# turbo.net
KiCad netlist of a schematic drawn in EAGLE
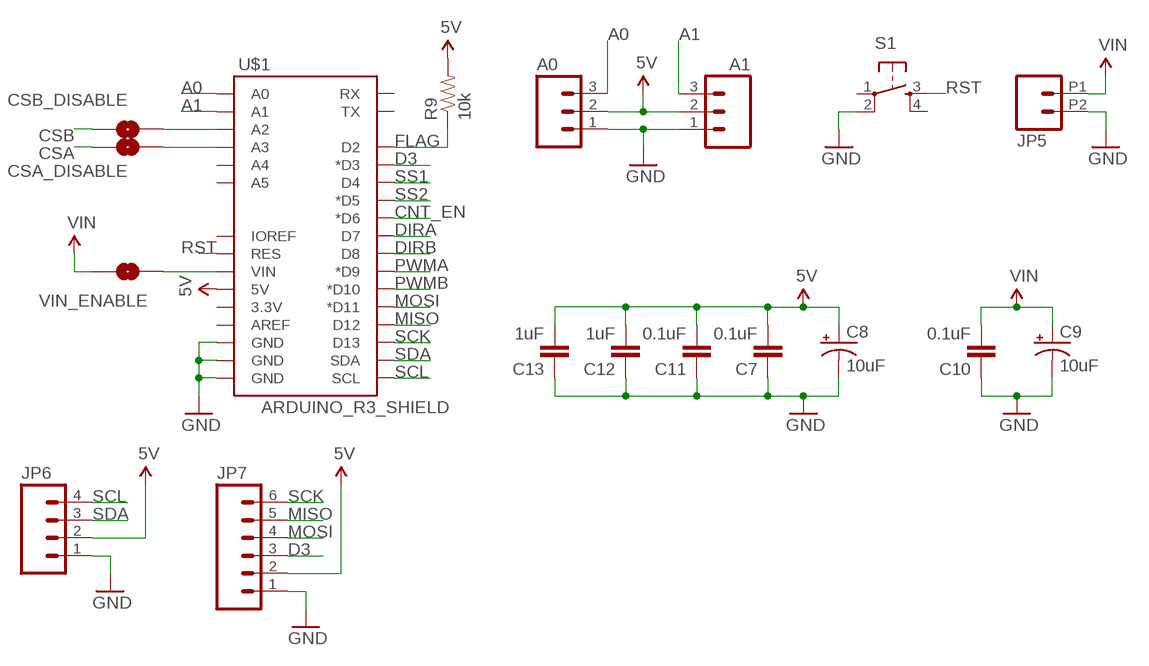
[diagram p0: schematic, sheet 1]
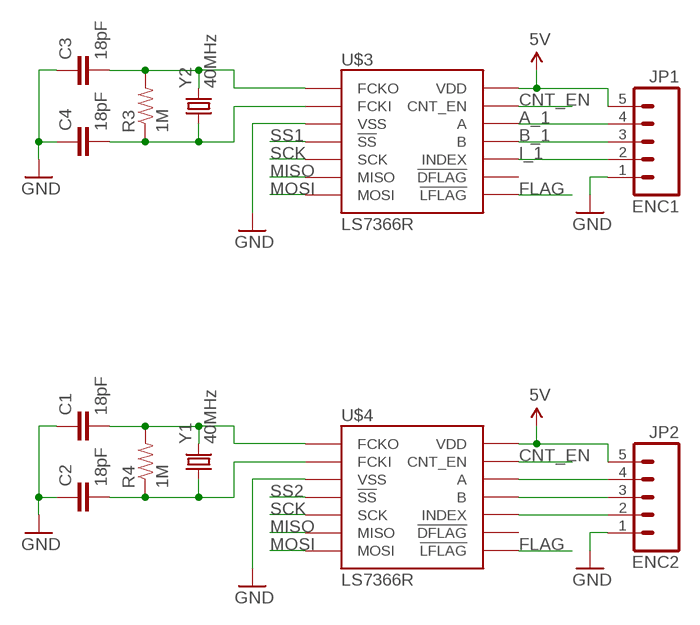
[diagram p1: schematic, sheet 2]
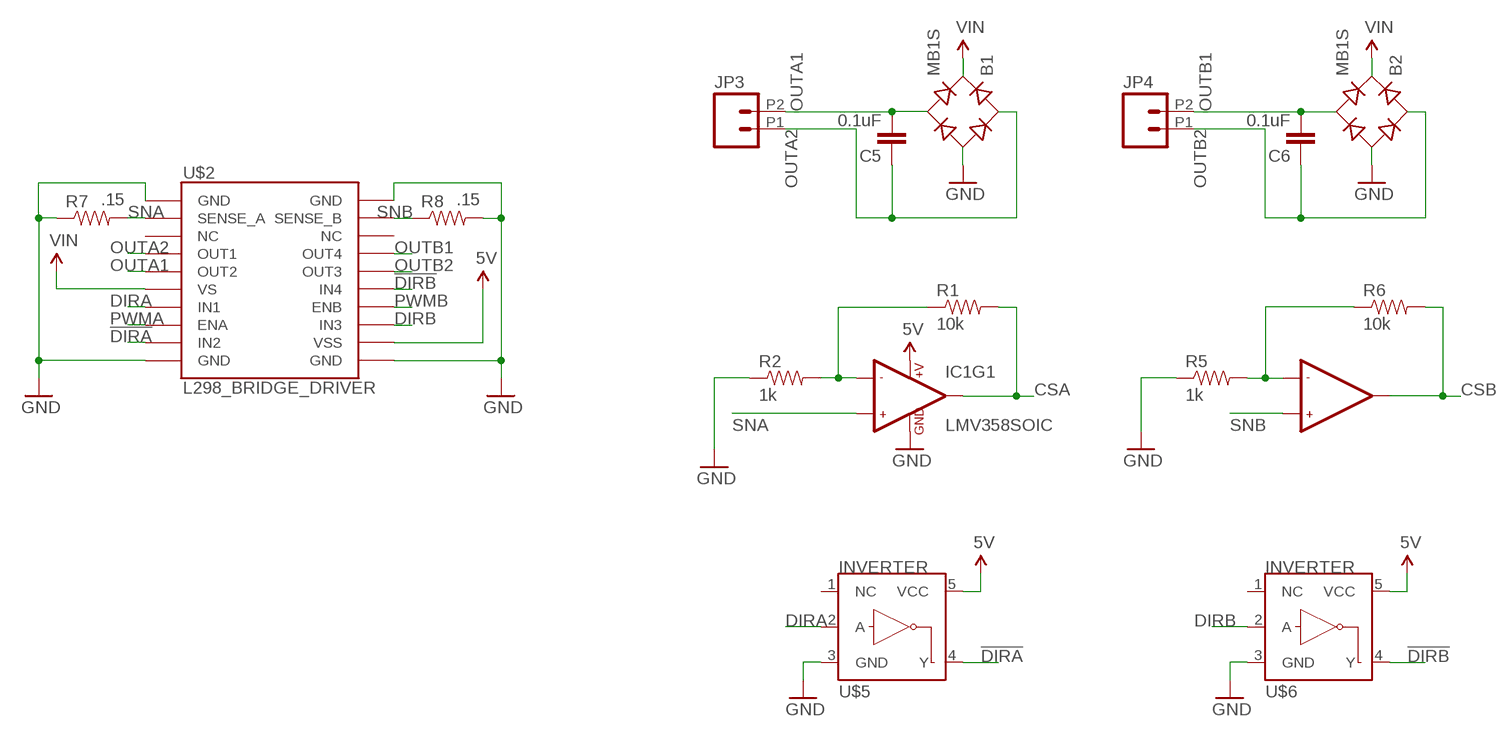
[diagram p2: schematic, sheet 3]

(export (version "E")
  (design (tool "Eeschema 10.0.6"))
  (components
    (comp (ref "B1")
      (value "MB1S")
      (footprint "eagle-import:SOIC-4")
      (libsource (lib "eagle-import") (part "MBS1"))
    )
    (comp (ref "B2")
      (value "MB1S")
      (footprint "eagle-import:SOIC-4")
      (libsource (lib "eagle-import") (part "MBS1"))
    )
    (comp (ref "C5")
      (value "0.1uF")
      (footprint "eagle-import:0603-CAP")
      (libsource (lib "eagle-import") (part "CAP0603-CAP"))
    )
    (comp (ref "C6")
      (value "0.1uF")
      (footprint "eagle-import:0603-CAP")
      (libsource (lib "eagle-import") (part "CAP0603-CAP"))
    )
    (comp (ref "IC1")
      (value "LMV358SOIC")
      (footprint "eagle-import:SO08")
      (libsource (lib "eagle-import") (part "LMV358SOIC"))
    )
    (comp (ref "JP3")
      (value "M022.54MM_SCREWTERM")
      (footprint "eagle-import:1X02_2.54_SCREWTERM")
      (libsource (lib "eagle-import") (part "M022.54MM_SCREWTERM"))
    )
    (comp (ref "JP4")
      (value "M022.54MM_SCREWTERM")
      (footprint "eagle-import:1X02_2.54_SCREWTERM")
      (libsource (lib "eagle-import") (part "M022.54MM_SCREWTERM"))
    )
    (comp (ref "R1")
      (value "10k")
      (footprint "eagle-import:0603-RES")
      (libsource (lib "eagle-import") (part "RESISTOR0603-RES"))
    )
    (comp (ref "R2")
      (value "1k")
      (footprint "eagle-import:0603-RES")
      (libsource (lib "eagle-import") (part "RESISTOR0603-RES"))
    )
    (comp (ref "R5")
      (value "1k")
      (footprint "eagle-import:0603-RES")
      (libsource (lib "eagle-import") (part "RESISTOR0603-RES"))
    )
    (comp (ref "R6")
      (value "10k")
      (footprint "eagle-import:0603-RES")
      (libsource (lib "eagle-import") (part "RESISTOR0603-RES"))
    )
    (comp (ref "R7")
      (value ".15")
      (footprint "eagle-import:1206")
      (libsource (lib "eagle-import") (part "SparkFun-Resistors_RESISTOR1206"))
    )
    (comp (ref "R8")
      (value ".15")
      (footprint "eagle-import:1206")
      (libsource (lib "eagle-import") (part "SparkFun-Resistors_RESISTOR1206"))
    )
    (comp (ref "U$2")
      (value "L298_BRIDGE_DRIVER")
      (footprint "eagle-import:POWERSO20")
      (libsource (lib "eagle-import") (part "L298_BRIDGE_DRIVER"))
    )
    (comp (ref "U$5")
      (value "INVERTER")
      (footprint "eagle-import:SOT23-5")
      (libsource (lib "eagle-import") (part "INVERTER"))
    )
    (comp (ref "U$6")
      (value "INVERTER")
      (footprint "eagle-import:SOT23-5")
      (libsource (lib "eagle-import") (part "INVERTER"))
    )
    (comp (ref "A0")
      (value "M03LOCK")
      (footprint "eagle-import:1X03_LOCK")
      (libsource (lib "eagle-import") (part "M03LOCK"))
    )
    (comp (ref "A1")
      (value "M03LOCK")
      (footprint "eagle-import:1X03_LOCK")
      (libsource (lib "eagle-import") (part "M03LOCK"))
    )
    (comp (ref "C7")
      (value "0.1uF")
      (footprint "eagle-import:0603-CAP")
      (libsource (lib "eagle-import") (part "CAP0603-CAP"))
    )
    (comp (ref "C8")
      (value "10uF")
      (footprint "eagle-import:PANASONIC_C")
      (libsource (lib "eagle-import") (part "CAP_POLC"))
    )
    (comp (ref "C9")
      (value "10uF")
      (footprint "eagle-import:PANASONIC_C")
      (libsource (lib "eagle-import") (part "CAP_POLC"))
    )
    (comp (ref "C10")
      (value "0.1uF")
      (footprint "eagle-import:0603-CAP")
      (libsource (lib "eagle-import") (part "CAP0603-CAP"))
    )
    (comp (ref "C11")
      (value "0.1uF")
      (footprint "eagle-import:0603-CAP")
      (libsource (lib "eagle-import") (part "CAP0603-CAP"))
    )
    (comp (ref "C12")
      (value "1uF")
      (footprint "eagle-import:0603-CAP")
      (libsource (lib "eagle-import") (part "CAP0603-CAP"))
    )
    (comp (ref "C13")
      (value "1uF")
      (footprint "eagle-import:0603-CAP")
      (libsource (lib "eagle-import") (part "CAP0603-CAP"))
    )
    (comp (ref "CSA_DISABLE")
      (value "SOLDERJUMPERTRACE")
      (footprint "eagle-import:SJ_2S-TRACE")
      (libsource (lib "eagle-import") (part "SOLDERJUMPERTRACE"))
    )
    (comp (ref "CSB_DISABLE")
      (value "SOLDERJUMPERTRACE")
      (footprint "eagle-import:SJ_2S-TRACE")
      (libsource (lib "eagle-import") (part "SOLDERJUMPERTRACE"))
    )
    (comp (ref "JP5")
      (value "M022.54MM_SCREWTERM")
      (footprint "eagle-import:1X02_2.54_SCREWTERM")
      (libsource (lib "eagle-import") (part "M022.54MM_SCREWTERM"))
    )
    (comp (ref "JP6")
      (value "M04POLAR_LOCK")
      (footprint "eagle-import:MOLEX-1X4_LOCK")
      (libsource (lib "eagle-import") (part "M04POLAR_LOCK"))
    )
    (comp (ref "JP7")
      (value "M06POLAR_LOCK")
      (footprint "eagle-import:MOLEX-1X6_LOCK")
      (libsource (lib "eagle-import") (part "M06POLAR_LOCK"))
    )
    (comp (ref "R9")
      (value "10k")
      (footprint "eagle-import:0603-RES")
      (libsource (lib "eagle-import") (part "RESISTOR0603-RES"))
    )
    (comp (ref "S1")
      (value "TAC_SWITCHSMD")
      (footprint "eagle-import:TACTILE_SWITCH_SMD")
      (libsource (lib "eagle-import") (part "TAC_SWITCHSMD"))
    )
    (comp (ref "U$1")
      (value "ARDUINO_R3_SHIELD")
      (footprint "eagle-import:UNO_R3_SHIELD")
      (libsource (lib "eagle-import") (part "ARDUINO_R3_SHIELD"))
    )
    (comp (ref "VIN_ENABLE")
      (value "SOLDERJUMPERNO")
      (footprint "eagle-import:SJ_2S-NO")
      (libsource (lib "eagle-import") (part "SOLDERJUMPERNO"))
    )
    (comp (ref "C1")
      (value "18pF")
      (footprint "eagle-import:0603-CAP")
      (libsource (lib "eagle-import") (part "CAP0603-CAP"))
    )
    (comp (ref "C2")
      (value "18pF")
      (footprint "eagle-import:0603-CAP")
      (libsource (lib "eagle-import") (part "CAP0603-CAP"))
    )
    (comp (ref "C3")
      (value "18pF")
      (footprint "eagle-import:0603-CAP")
      (libsource (lib "eagle-import") (part "CAP0603-CAP"))
    )
    (comp (ref "C4")
      (value "18pF")
      (footprint "eagle-import:0603-CAP")
      (libsource (lib "eagle-import") (part "CAP0603-CAP"))
    )
    (comp (ref "JP1")
      (value "ENC1")
      (footprint "eagle-import:1X05_LOCK")
      (libsource (lib "eagle-import") (part "M05LOCK"))
    )
    (comp (ref "JP2")
      (value "ENC2")
      (footprint "eagle-import:1X05_LOCK")
      (libsource (lib "eagle-import") (part "M05LOCK"))
    )
    (comp (ref "R3")
      (value "1M")
      (footprint "eagle-import:0603-RES")
      (libsource (lib "eagle-import") (part "RESISTOR0603-RES"))
    )
    (comp (ref "R4")
      (value "1M")
      (footprint "eagle-import:0603-RES")
      (libsource (lib "eagle-import") (part "RESISTOR0603-RES"))
    )
    (comp (ref "U$3")
      (value "LS7366R")
      (footprint "eagle-import:SOIC14")
      (libsource (lib "eagle-import") (part "LS7366R"))
    )
    (comp (ref "U$4")
      (value "LS7366R")
      (footprint "eagle-import:SOIC14")
      (libsource (lib "eagle-import") (part "LS7366R"))
    )
    (comp (ref "Y1")
      (value "40MHz")
      (footprint "eagle-import:CRYSTAL-SMD-5X3")
      (libsource (lib "eagle-import") (part "CRYSTAL5X3"))
    )
    (comp (ref "Y2")
      (value "40MHz")
      (footprint "eagle-import:CRYSTAL-SMD-5X3")
      (libsource (lib "eagle-import") (part "CRYSTAL5X3"))
    )
  )
  (nets
    (net (code "1") (name "5V") (class "Default")
      (node (ref "A0") (pin "2") (pinfunction "2_2") (pintype "passive"))
      (node (ref "A1") (pin "2") (pinfunction "2_2") (pintype "passive"))
      (node (ref "C11") (pin "2") (pinfunction "2_2") (pintype "passive"))
      (node (ref "C12") (pin "2") (pinfunction "2_2") (pintype "passive"))
      (node (ref "C13") (pin "2") (pinfunction "2_2") (pintype "passive"))
      (node (ref "C7") (pin "2") (pinfunction "2_2") (pintype "passive"))
      (node (ref "C8") (pin "+") (pinfunction "+_+") (pintype "passive"))
      (node (ref "IC1") (pin "8") (pinfunction "+V_8") (pintype "power_in"))
      (node (ref "JP1") (pin "5") (pinfunction "5_5") (pintype "passive"))
      (node (ref "JP2") (pin "5") (pinfunction "5_5") (pintype "passive"))
      (node (ref "JP6") (pin "2") (pinfunction "2_2") (pintype "passive"))
      (node (ref "JP7") (pin "2") (pinfunction "2_2") (pintype "passive"))
      (node (ref "R9") (pin "2") (pinfunction "2_2") (pintype "passive"))
      (node (ref "U$1") (pin "5V") (pinfunction "5V_5V") (pintype "bidirectional"))
      (node (ref "U$2") (pin "12") (pinfunction "VSS_12") (pintype "bidirectional"))
      (node (ref "U$3") (pin "14") (pinfunction "VDD_14") (pintype "bidirectional"))
      (node (ref "U$4") (pin "14") (pinfunction "VDD_14") (pintype "bidirectional"))
      (node (ref "U$5") (pin "5") (pinfunction "VCC_5") (pintype "bidirectional"))
      (node (ref "U$6") (pin "5") (pinfunction "VCC_5") (pintype "bidirectional"))
    )
    (net (code "2") (name "A0") (class "Default")
      (node (ref "A0") (pin "3") (pinfunction "3_3") (pintype "passive"))
      (node (ref "U$1") (pin "A0") (pinfunction "A0_A0") (pintype "bidirectional"))
    )
    (net (code "3") (name "A1") (class "Default")
      (node (ref "A1") (pin "3") (pinfunction "3_3") (pintype "passive"))
      (node (ref "U$1") (pin "A1") (pinfunction "A1_A1") (pintype "bidirectional"))
    )
    (net (code "4") (name "A_1") (class "Default")
      (node (ref "JP1") (pin "4") (pinfunction "4_4") (pintype "passive"))
      (node (ref "U$3") (pin "12") (pinfunction "A_12") (pintype "bidirectional"))
    )
    (net (code "5") (name "B_1") (class "Default")
      (node (ref "JP1") (pin "3") (pinfunction "3_3") (pintype "passive"))
      (node (ref "U$3") (pin "11") (pinfunction "B_11") (pintype "bidirectional"))
    )
    (net (code "6") (name "CNT_EN") (class "Default")
      (node (ref "U$1") (pin "D6") (pinfunction "*D6_D6") (pintype "bidirectional"))
      (node (ref "U$3") (pin "13") (pinfunction "CNT_EN_13") (pintype "bidirectional"))
      (node (ref "U$4") (pin "13") (pinfunction "CNT_EN_13") (pintype "bidirectional"))
    )
    (net (code "7") (name "CSA") (class "Default")
      (node (ref "CSA_DISABLE") (pin "2") (pinfunction "2_2") (pintype "passive"))
      (node (ref "IC1") (pin "1") (pinfunction "OUT1_1") (pintype "output"))
      (node (ref "R1") (pin "2") (pinfunction "2_2") (pintype "passive"))
    )
    (net (code "8") (name "CSB") (class "Default")
      (node (ref "CSB_DISABLE") (pin "2") (pinfunction "2_2") (pintype "passive"))
      (node (ref "IC1") (pin "7") (pinfunction "OUT2_7") (pintype "output"))
      (node (ref "R6") (pin "2") (pinfunction "2_2") (pintype "passive"))
    )
    (net (code "9") (name "D3") (class "Default")
      (node (ref "JP7") (pin "3") (pinfunction "3_3") (pintype "passive"))
      (node (ref "U$1") (pin "D3") (pinfunction "*D3_D3") (pintype "bidirectional"))
    )
    (net (code "10") (name "DIRA") (class "Default")
      (node (ref "U$1") (pin "D7") (pinfunction "D7_D7") (pintype "bidirectional"))
      (node (ref "U$2") (pin "7") (pinfunction "IN1_7") (pintype "bidirectional"))
      (node (ref "U$5") (pin "2") (pinfunction "A_2") (pintype "bidirectional"))
    )
    (net (code "11") (name "DIRB") (class "Default")
      (node (ref "U$1") (pin "D8") (pinfunction "D8_D8") (pintype "bidirectional"))
      (node (ref "U$2") (pin "13") (pinfunction "IN3_13") (pintype "bidirectional"))
      (node (ref "U$6") (pin "2") (pinfunction "A_2") (pintype "bidirectional"))
    )
    (net (code "12") (name "FLAG") (class "Default")
      (node (ref "R9") (pin "1") (pinfunction "1_1") (pintype "passive"))
      (node (ref "U$1") (pin "D2") (pinfunction "D2_D2") (pintype "bidirectional"))
      (node (ref "U$3") (pin "8") (pinfunction "~{LFLAG}_8") (pintype "bidirectional"))
      (node (ref "U$4") (pin "8") (pinfunction "~{LFLAG}_8") (pintype "bidirectional"))
    )
    (net (code "13") (name "GND") (class "Default")
      (node (ref "A0") (pin "1") (pinfunction "1_1") (pintype "passive"))
      (node (ref "A1") (pin "1") (pinfunction "1_1") (pintype "passive"))
      (node (ref "B1") (pin "-") (pinfunction "-_-") (pintype "passive"))
      (node (ref "B2") (pin "-") (pinfunction "-_-") (pintype "passive"))
      (node (ref "C1") (pin "1") (pinfunction "1_1") (pintype "passive"))
      (node (ref "C10") (pin "1") (pinfunction "1_1") (pintype "passive"))
      (node (ref "C11") (pin "1") (pinfunction "1_1") (pintype "passive"))
      (node (ref "C12") (pin "1") (pinfunction "1_1") (pintype "passive"))
      (node (ref "C13") (pin "1") (pinfunction "1_1") (pintype "passive"))
      (node (ref "C2") (pin "1") (pinfunction "1_1") (pintype "passive"))
      (node (ref "C3") (pin "1") (pinfunction "1_1") (pintype "passive"))
      (node (ref "C4") (pin "1") (pinfunction "1_1") (pintype "passive"))
      (node (ref "C7") (pin "1") (pinfunction "1_1") (pintype "passive"))
      (node (ref "C8") (pin "-") (pinfunction "-_-") (pintype "passive"))
      (node (ref "C9") (pin "-") (pinfunction "-_-") (pintype "passive"))
      (node (ref "IC1") (pin "4") (pinfunction "GND_4") (pintype "power_in"))
      (node (ref "JP1") (pin "1") (pinfunction "1_1") (pintype "passive"))
      (node (ref "JP2") (pin "1") (pinfunction "1_1") (pintype "passive"))
      (node (ref "JP5") (pin "P2") (pinfunction "2_P2") (pintype "passive"))
      (node (ref "JP6") (pin "1") (pinfunction "1_1") (pintype "passive"))
      (node (ref "JP7") (pin "1") (pinfunction "1_1") (pintype "passive"))
      (node (ref "R2") (pin "1") (pinfunction "1_1") (pintype "passive"))
      (node (ref "R5") (pin "1") (pinfunction "1_1") (pintype "passive"))
      (node (ref "R7") (pin "1") (pinfunction "1_1") (pintype "passive"))
      (node (ref "R8") (pin "2") (pinfunction "2_2") (pintype "passive"))
      (node (ref "S1") (pin "2") (pinfunction "2_2") (pintype "passive"))
      (node (ref "U$1") (pin "GND@0") (pinfunction "GND_GND@0") (pintype "bidirectional"))
      (node (ref "U$1") (pin "GND@1") (pinfunction "GND_GND@1") (pintype "bidirectional"))
      (node (ref "U$1") (pin "GND@2") (pinfunction "GND_GND@2") (pintype "bidirectional"))
      (node (ref "U$2") (pin "1") (pinfunction "GND_1") (pintype "bidirectional"))
      (node (ref "U$2") (pin "10") (pinfunction "GND_10") (pintype "bidirectional"))
      (node (ref "U$2") (pin "11") (pinfunction "GND_11") (pintype "bidirectional"))
      (node (ref "U$2") (pin "20") (pinfunction "GND_20") (pintype "bidirectional"))
      (node (ref "U$2") (pin "P$1") (pinfunction "GND_P$1") (pintype "bidirectional"))
      (node (ref "U$3") (pin "3") (pinfunction "VSS_3") (pintype "bidirectional"))
      (node (ref "U$4") (pin "3") (pinfunction "VSS_3") (pintype "bidirectional"))
      (node (ref "U$5") (pin "3") (pinfunction "GND_3") (pintype "bidirectional"))
      (node (ref "U$6") (pin "3") (pinfunction "GND_3") (pintype "bidirectional"))
    )
    (net (code "14") (name "I_1") (class "Default")
      (node (ref "JP1") (pin "2") (pinfunction "2_2") (pintype "passive"))
      (node (ref "U$3") (pin "10") (pinfunction "INDEX_10") (pintype "bidirectional"))
    )
    (net (code "15") (name "MISO") (class "Default")
      (node (ref "JP7") (pin "5") (pinfunction "5_5") (pintype "passive"))
      (node (ref "U$1") (pin "D12") (pinfunction "D12_D12") (pintype "bidirectional"))
      (node (ref "U$3") (pin "6") (pinfunction "MISO_6") (pintype "bidirectional"))
      (node (ref "U$4") (pin "6") (pinfunction "MISO_6") (pintype "bidirectional"))
    )
    (net (code "16") (name "MOSI") (class "Default")
      (node (ref "JP7") (pin "4") (pinfunction "4_4") (pintype "passive"))
      (node (ref "U$1") (pin "D11") (pinfunction "*D11_D11") (pintype "bidirectional"))
      (node (ref "U$3") (pin "7") (pinfunction "MOSI_7") (pintype "bidirectional"))
      (node (ref "U$4") (pin "7") (pinfunction "MOSI_7") (pintype "bidirectional"))
    )
    (net (code "17") (name "Net-(CSA_DISABLE-Pad1)") (class "Default")
      (node (ref "CSA_DISABLE") (pin "1") (pinfunction "1_1") (pintype "passive"))
      (node (ref "U$1") (pin "A3") (pinfunction "A3_A3") (pintype "bidirectional"))
    )
    (net (code "18") (name "Net-(CSB_DISABLE-Pad1)") (class "Default")
      (node (ref "CSB_DISABLE") (pin "1") (pinfunction "1_1") (pintype "passive"))
      (node (ref "U$1") (pin "A2") (pinfunction "A2_A2") (pintype "bidirectional"))
    )
    (net (code "19") (name "Net-(IC1A--IN1)") (class "Default")
      (node (ref "IC1") (pin "2") (pinfunction "-IN1_2") (pintype "input"))
      (node (ref "R1") (pin "1") (pinfunction "1_1") (pintype "passive"))
      (node (ref "R2") (pin "2") (pinfunction "2_2") (pintype "passive"))
    )
    (net (code "20") (name "Net-(IC1B--IN2)") (class "Default")
      (node (ref "IC1") (pin "6") (pinfunction "-IN2_6") (pintype "input"))
      (node (ref "R5") (pin "2") (pinfunction "2_2") (pintype "passive"))
      (node (ref "R6") (pin "1") (pinfunction "1_1") (pintype "passive"))
    )
    (net (code "21") (name "Net-(U$1-PadVIN)") (class "Default")
      (node (ref "U$1") (pin "VIN") (pinfunction "VIN_VIN") (pintype "bidirectional"))
      (node (ref "VIN_ENABLE") (pin "2") (pinfunction "2_2") (pintype "passive"))
    )
    (net (code "22") (name "Net-(U$3-FCKI)") (class "Default")
      (node (ref "C4") (pin "2") (pinfunction "2_2") (pintype "passive"))
      (node (ref "R3") (pin "1") (pinfunction "1_1") (pintype "passive"))
      (node (ref "U$3") (pin "2") (pinfunction "FCKI_2") (pintype "bidirectional"))
      (node (ref "Y2") (pin "1") (pinfunction "1_1") (pintype "passive"))
    )
    (net (code "23") (name "Net-(U$3-FCKO)") (class "Default")
      (node (ref "C3") (pin "2") (pinfunction "2_2") (pintype "passive"))
      (node (ref "R3") (pin "2") (pinfunction "2_2") (pintype "passive"))
      (node (ref "U$3") (pin "1") (pinfunction "FCKO_1") (pintype "bidirectional"))
      (node (ref "Y2") (pin "3") (pinfunction "2_3") (pintype "passive"))
    )
    (net (code "24") (name "Net-(U$4-A)") (class "Default")
      (node (ref "JP2") (pin "4") (pinfunction "4_4") (pintype "passive"))
      (node (ref "U$4") (pin "12") (pinfunction "A_12") (pintype "bidirectional"))
    )
    (net (code "25") (name "Net-(U$4-B)") (class "Default")
      (node (ref "JP2") (pin "3") (pinfunction "3_3") (pintype "passive"))
      (node (ref "U$4") (pin "11") (pinfunction "B_11") (pintype "bidirectional"))
    )
    (net (code "26") (name "Net-(U$4-FCKI)") (class "Default")
      (node (ref "C2") (pin "2") (pinfunction "2_2") (pintype "passive"))
      (node (ref "R4") (pin "1") (pinfunction "1_1") (pintype "passive"))
      (node (ref "U$4") (pin "2") (pinfunction "FCKI_2") (pintype "bidirectional"))
      (node (ref "Y1") (pin "1") (pinfunction "1_1") (pintype "passive"))
    )
    (net (code "27") (name "Net-(U$4-FCKO)") (class "Default")
      (node (ref "C1") (pin "2") (pinfunction "2_2") (pintype "passive"))
      (node (ref "R4") (pin "2") (pinfunction "2_2") (pintype "passive"))
      (node (ref "U$4") (pin "1") (pinfunction "FCKO_1") (pintype "bidirectional"))
      (node (ref "Y1") (pin "3") (pinfunction "2_3") (pintype "passive"))
    )
    (net (code "28") (name "Net-(U$4-INDEX)") (class "Default")
      (node (ref "JP2") (pin "2") (pinfunction "2_2") (pintype "passive"))
      (node (ref "U$4") (pin "10") (pinfunction "INDEX_10") (pintype "bidirectional"))
    )
    (net (code "29") (name "OUTA1") (class "Default")
      (node (ref "B1") (pin "~2") (pinfunction "AC2_~2") (pintype "passive"))
      (node (ref "C5") (pin "2") (pinfunction "2_2") (pintype "passive"))
      (node (ref "JP3") (pin "P2") (pinfunction "2_P2") (pintype "passive"))
      (node (ref "U$2") (pin "5") (pinfunction "OUT2_5") (pintype "bidirectional"))
    )
    (net (code "30") (name "OUTA2") (class "Default")
      (node (ref "B1") (pin "~1") (pinfunction "AC1_~1") (pintype "passive"))
      (node (ref "C5") (pin "1") (pinfunction "1_1") (pintype "passive"))
      (node (ref "JP3") (pin "P1") (pinfunction "1_P1") (pintype "passive"))
      (node (ref "U$2") (pin "4") (pinfunction "OUT1_4") (pintype "bidirectional"))
    )
    (net (code "31") (name "OUTB1") (class "Default")
      (node (ref "B2") (pin "~2") (pinfunction "AC2_~2") (pintype "passive"))
      (node (ref "C6") (pin "2") (pinfunction "2_2") (pintype "passive"))
      (node (ref "JP4") (pin "P2") (pinfunction "2_P2") (pintype "passive"))
      (node (ref "U$2") (pin "17") (pinfunction "OUT4_17") (pintype "bidirectional"))
    )
    (net (code "32") (name "OUTB2") (class "Default")
      (node (ref "B2") (pin "~1") (pinfunction "AC1_~1") (pintype "passive"))
      (node (ref "C6") (pin "1") (pinfunction "1_1") (pintype "passive"))
      (node (ref "JP4") (pin "P1") (pinfunction "1_P1") (pintype "passive"))
      (node (ref "U$2") (pin "16") (pinfunction "OUT3_16") (pintype "bidirectional"))
    )
    (net (code "33") (name "PWMA") (class "Default")
      (node (ref "U$1") (pin "D9") (pinfunction "*D9_D9") (pintype "bidirectional"))
      (node (ref "U$2") (pin "8") (pinfunction "ENA_8") (pintype "bidirectional"))
    )
    (net (code "34") (name "PWMB") (class "Default")
      (node (ref "U$1") (pin "D10") (pinfunction "*D10_D10") (pintype "bidirectional"))
      (node (ref "U$2") (pin "14") (pinfunction "ENB_14") (pintype "bidirectional"))
    )
    (net (code "35") (name "RST") (class "Default")
      (node (ref "S1") (pin "3") (pinfunction "3_3") (pintype "passive"))
      (node (ref "U$1") (pin "RES") (pinfunction "RES_RES") (pintype "bidirectional"))
    )
    (net (code "36") (name "SCK") (class "Default")
      (node (ref "JP7") (pin "6") (pinfunction "6_6") (pintype "passive"))
      (node (ref "U$1") (pin "D13") (pinfunction "D13_D13") (pintype "bidirectional"))
      (node (ref "U$3") (pin "5") (pinfunction "SCK_5") (pintype "bidirectional"))
      (node (ref "U$4") (pin "5") (pinfunction "SCK_5") (pintype "bidirectional"))
    )
    (net (code "37") (name "SCL") (class "Default")
      (node (ref "JP6") (pin "4") (pinfunction "4_4") (pintype "passive"))
      (node (ref "U$1") (pin "SCL") (pinfunction "SCL_SCL") (pintype "bidirectional"))
    )
    (net (code "38") (name "SDA") (class "Default")
      (node (ref "JP6") (pin "3") (pinfunction "3_3") (pintype "passive"))
      (node (ref "U$1") (pin "SDA") (pinfunction "SDA_SDA") (pintype "bidirectional"))
    )
    (net (code "39") (name "SNA") (class "Default")
      (node (ref "IC1") (pin "3") (pinfunction "+IN1_3") (pintype "input"))
      (node (ref "R7") (pin "2") (pinfunction "2_2") (pintype "passive"))
      (node (ref "U$2") (pin "2") (pinfunction "SENSE_A_2") (pintype "bidirectional"))
    )
    (net (code "40") (name "SNB") (class "Default")
      (node (ref "IC1") (pin "5") (pinfunction "+IN2_5") (pintype "input"))
      (node (ref "R8") (pin "1") (pinfunction "1_1") (pintype "passive"))
      (node (ref "U$2") (pin "19") (pinfunction "SENSE_B_19") (pintype "bidirectional"))
    )
    (net (code "41") (name "SS1") (class "Default")
      (node (ref "U$1") (pin "D4") (pinfunction "D4_D4") (pintype "bidirectional"))
      (node (ref "U$3") (pin "4") (pinfunction "~{SS}_4") (pintype "bidirectional"))
    )
    (net (code "42") (name "SS2") (class "Default")
      (node (ref "U$1") (pin "D5") (pinfunction "*D5_D5") (pintype "bidirectional"))
      (node (ref "U$4") (pin "4") (pinfunction "~{SS}_4") (pintype "bidirectional"))
    )
    (net (code "43") (name "VIN") (class "Default")
      (node (ref "B1") (pin "+") (pinfunction "+_+") (pintype "passive"))
      (node (ref "B2") (pin "+") (pinfunction "+_+") (pintype "passive"))
      (node (ref "C10") (pin "2") (pinfunction "2_2") (pintype "passive"))
      (node (ref "C9") (pin "+") (pinfunction "+_+") (pintype "passive"))
      (node (ref "JP5") (pin "P1") (pinfunction "1_P1") (pintype "passive"))
      (node (ref "U$2") (pin "6") (pinfunction "VS_6") (pintype "bidirectional"))
      (node (ref "VIN_ENABLE") (pin "1") (pinfunction "1_1") (pintype "passive"))
    )
    (net (code "44") (name "unconnected-(S1-Pad1)") (class "Default")
      (node (ref "S1") (pin "1") (pinfunction "1_1") (pintype "passive"))
    )
    (net (code "45") (name "unconnected-(S1-Pad4)") (class "Default")
      (node (ref "S1") (pin "4") (pinfunction "4_4") (pintype "passive"))
    )
    (net (code "46") (name "unconnected-(U$1-Pad3.3V)") (class "Default")
      (node (ref "U$1") (pin "3.3V") (pinfunction "3.3V_3.3V") (pintype "bidirectional"))
    )
    (net (code "47") (name "unconnected-(U$1-PadA4)") (class "Default")
      (node (ref "U$1") (pin "A4") (pinfunction "A4_A4") (pintype "bidirectional"))
    )
    (net (code "48") (name "unconnected-(U$1-PadA5)") (class "Default")
      (node (ref "U$1") (pin "A5") (pinfunction "A5_A5") (pintype "bidirectional"))
    )
    (net (code "49") (name "unconnected-(U$1-PadAREF)") (class "Default")
      (node (ref "U$1") (pin "AREF") (pinfunction "AREF_AREF") (pintype "bidirectional"))
    )
    (net (code "50") (name "unconnected-(U$1-PadIOREF)") (class "Default")
      (node (ref "U$1") (pin "IOREF") (pinfunction "IOREF_IOREF") (pintype "bidirectional"))
    )
    (net (code "51") (name "unconnected-(U$1-PadRX)") (class "Default")
      (node (ref "U$1") (pin "RX") (pinfunction "RX_RX") (pintype "bidirectional"))
    )
    (net (code "52") (name "unconnected-(U$1-PadTX)") (class "Default")
      (node (ref "U$1") (pin "TX") (pinfunction "TX_TX") (pintype "bidirectional"))
    )
    (net (code "53") (name "unconnected-(U$2-NC-Pad3)") (class "Default")
      (node (ref "U$2") (pin "3") (pinfunction "NC_3") (pintype "bidirectional"))
    )
    (net (code "54") (name "unconnected-(U$2-NC-Pad18)") (class "Default")
      (node (ref "U$2") (pin "18") (pinfunction "NC_18") (pintype "bidirectional"))
    )
    (net (code "55") (name "unconnected-(U$3-~{DFLAG}-Pad9)") (class "Default")
      (node (ref "U$3") (pin "9") (pinfunction "~{DFLAG}_9") (pintype "bidirectional"))
    )
    (net (code "56") (name "unconnected-(U$4-~{DFLAG}-Pad9)") (class "Default")
      (node (ref "U$4") (pin "9") (pinfunction "~{DFLAG}_9") (pintype "bidirectional"))
    )
    (net (code "57") (name "unconnected-(U$5-NC-Pad1)") (class "Default")
      (node (ref "U$5") (pin "1") (pinfunction "NC_1") (pintype "bidirectional"))
    )
    (net (code "58") (name "unconnected-(U$6-NC-Pad1)") (class "Default")
      (node (ref "U$6") (pin "1") (pinfunction "NC_1") (pintype "bidirectional"))
    )
    (net (code "59") (name "~{DIRA}") (class "Default")
      (node (ref "U$2") (pin "9") (pinfunction "IN2_9") (pintype "bidirectional"))
      (node (ref "U$5") (pin "4") (pinfunction "Y_4") (pintype "bidirectional"))
    )
    (net (code "60") (name "~{DIRB}") (class "Default")
      (node (ref "U$2") (pin "15") (pinfunction "IN4_15") (pintype "bidirectional"))
      (node (ref "U$6") (pin "4") (pinfunction "Y_4") (pintype "bidirectional"))
    )
  )
)
